# 9_rs485.net
KiCad netlist of a schematic drawn in Altium Designer
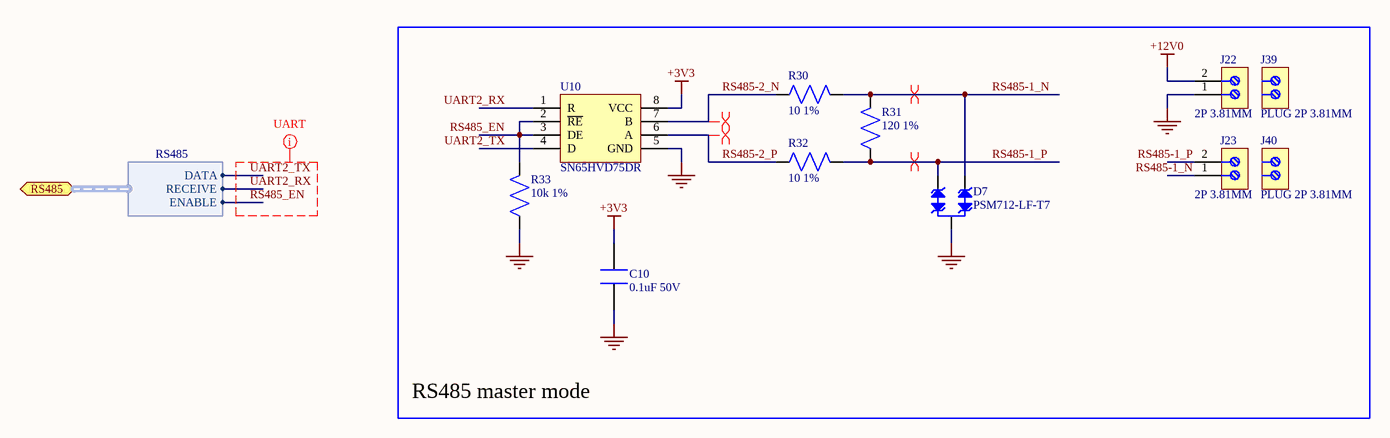
[diagram p0: 9_rs485.SchDoc]

(export (version "E")
  (design (tool "Eeschema 10.0.6"))
  (components
    (comp (ref "C10")
      (value "0.1uF 50V")
      (footprint "C0603")
      (description "X7R 100nF ±10% 50V 0603 Multilayer Ceramic Capacitors MLCC - SMD/SMT")
      (fields (field (name "LCSC PART") "C14663"))
      (libsource (lib "nombre_por_definir") (part "CC0603KRX7R9BB104"))
    )
    (comp (ref "D7")
      (value "PSM712-LF-T7")
      (footprint "SOT-23-3")
      (description "Bidirectional - 19V 13.3V 12V SOT-23(SOT-23-3) TVS")
      (fields (field (name "LCSC PART") "C32677"))
      (libsource (lib "nombre_por_definir") (part "PSM712-LF-T7"))
    )
    (comp (ref "J22")
      (value "2P 3.81MM")
      (footprint "TB-2P-3.81MM")
      (description "Terminal Block 2 Positions 3.81MM")
      (libsource (lib "nombre_por_definir") (part "TBLOCK-2P-3.81MM"))
    )
    (comp (ref "J23")
      (value "2P 3.81MM")
      (footprint "TB-2P-3.81MM")
      (description "Terminal Block 2 Positions 3.81MM")
      (libsource (lib "nombre_por_definir") (part "TBLOCK-2P-3.81MM"))
    )
    (comp (ref "J39")
      (value "PLUG 2P 3.81MM")
      (footprint "TB-PLUG-2P-3.81MM")
      (description "Terminal block plug 2positions 3.81mm")
      (libsource (lib "nombre_por_definir") (part "PLUG-2P-3.81MM"))
    )
    (comp (ref "J40")
      (value "PLUG 2P 3.81MM")
      (footprint "TB-PLUG-2P-3.81MM")
      (description "Terminal block plug 2positions 3.81mm")
      (libsource (lib "nombre_por_definir") (part "PLUG-2P-3.81MM"))
    )
    (comp (ref "R30")
      (value "10 1%")
      (footprint "R0603")
      (description "±1% ±400ppm/℃ 10Ω 0.1W 0603 Chip Resistor - Surface Mount")
      (fields (field (name "LCSC PART") "C22859"))
      (libsource (lib "nombre_por_definir") (part "0603WAF100JT5E"))
    )
    (comp (ref "R31")
      (value "120 1%")
      (footprint "R0603")
      (description "±1% ±100ppm/℃ 120Ω 0.1W 0603 Chip Resistor - Surface Mount")
      (fields (field (name "LCSC PART") "C22787"))
      (libsource (lib "nombre_por_definir") (part "0603WAF1200T5E"))
    )
    (comp (ref "R32")
      (value "10 1%")
      (footprint "R0603")
      (description "±1% ±400ppm/℃ 10Ω 0.1W 0603 Chip Resistor - Surface Mount")
      (fields (field (name "LCSC PART") "C22859"))
      (libsource (lib "nombre_por_definir") (part "0603WAF100JT5E"))
    )
    (comp (ref "R33")
      (value "10k 1%")
      (footprint "R0603")
      (description "±1% ±100ppm/℃ 10kΩ 0.1W 0603 Chip Resistor - Surface Mount")
      (fields (field (name "LCSC PART") "C25804"))
      (libsource (lib "nombre_por_definir") (part "0603WAF1002T5E"))
    )
    (comp (ref "U10")
      (value "SN65HVD75DR")
      (footprint "SOIC-8")
      (description "Transceiver 1/1 RS422, RS485 20Mbps SOIC-8_150mil RS-485/RS-422 ICs")
      (fields (field (name "LCSC PART") "C57928"))
      (libsource (lib "nombre_por_definir") (part "SN65HVD75DR"))
    )
  )
  (nets
    (net (code "2") (name "+3V3") (class "Default")
      (node (ref "C10") (pin "1") (pinfunction "1_1") (pintype "passive"))
      (node (ref "U10") (pin "8") (pinfunction "VCC_8") (pintype "passive"))
    )
    (net (code "3") (name "+12V0") (class "Default")
      (node (ref "J22") (pin "2") (pinfunction "2_2") (pintype "passive"))
    )
    (net (code "4") (name "/RS485-1_N") (class "Default")
      (node (ref "D7") (pin "2") (pinfunction "2_2") (pintype "passive"))
      (node (ref "J23") (pin "1") (pinfunction "1_1") (pintype "passive"))
      (node (ref "R30") (pin "2") (pinfunction "2_2") (pintype "passive"))
      (node (ref "R31") (pin "2") (pinfunction "2_2") (pintype "passive"))
    )
    (net (code "5") (name "/RS485-1_P") (class "Default")
      (node (ref "D7") (pin "1") (pinfunction "1_1") (pintype "passive"))
      (node (ref "J23") (pin "2") (pinfunction "2_2") (pintype "passive"))
      (node (ref "R31") (pin "1") (pinfunction "1_1") (pintype "passive"))
      (node (ref "R32") (pin "2") (pinfunction "2_2") (pintype "passive"))
    )
    (net (code "6") (name "/RS485-2_N") (class "Default")
      (node (ref "R30") (pin "1") (pinfunction "1_1") (pintype "passive"))
      (node (ref "U10") (pin "7") (pinfunction "B_7") (pintype "passive"))
    )
    (net (code "7") (name "/RS485-2_P") (class "Default")
      (node (ref "R32") (pin "1") (pinfunction "1_1") (pintype "passive"))
      (node (ref "U10") (pin "6") (pinfunction "A_6") (pintype "passive"))
    )
    (net (code "8") (name "/RS485_EN") (class "Default")
      (node (ref "R33") (pin "2") (pinfunction "2_2") (pintype "passive"))
      (node (ref "U10") (pin "2") (pinfunction "~{RE}_2") (pintype "passive"))
      (node (ref "U10") (pin "3") (pinfunction "DE_3") (pintype "passive"))
    )
    (net (code "9") (name "/UART2_RX") (class "Default")
      (node (ref "U10") (pin "1") (pinfunction "R_1") (pintype "passive"))
    )
    (net (code "10") (name "/UART2_TX") (class "Default")
      (node (ref "U10") (pin "4") (pinfunction "D_4") (pintype "passive"))
    )
    (net (code "12") (name "GND") (class "Default")
      (node (ref "C10") (pin "2") (pinfunction "2_2") (pintype "passive"))
      (node (ref "D7") (pin "3") (pinfunction "3_3") (pintype "passive"))
      (node (ref "J22") (pin "1") (pinfunction "1_1") (pintype "passive"))
      (node (ref "R33") (pin "1") (pinfunction "1_1") (pintype "passive"))
      (node (ref "U10") (pin "5") (pinfunction "GND_5") (pintype "passive"))
    )
  )
)
